# PCB-ACMSLb.net
KiCad netlist of a schematic drawn in EAGLE
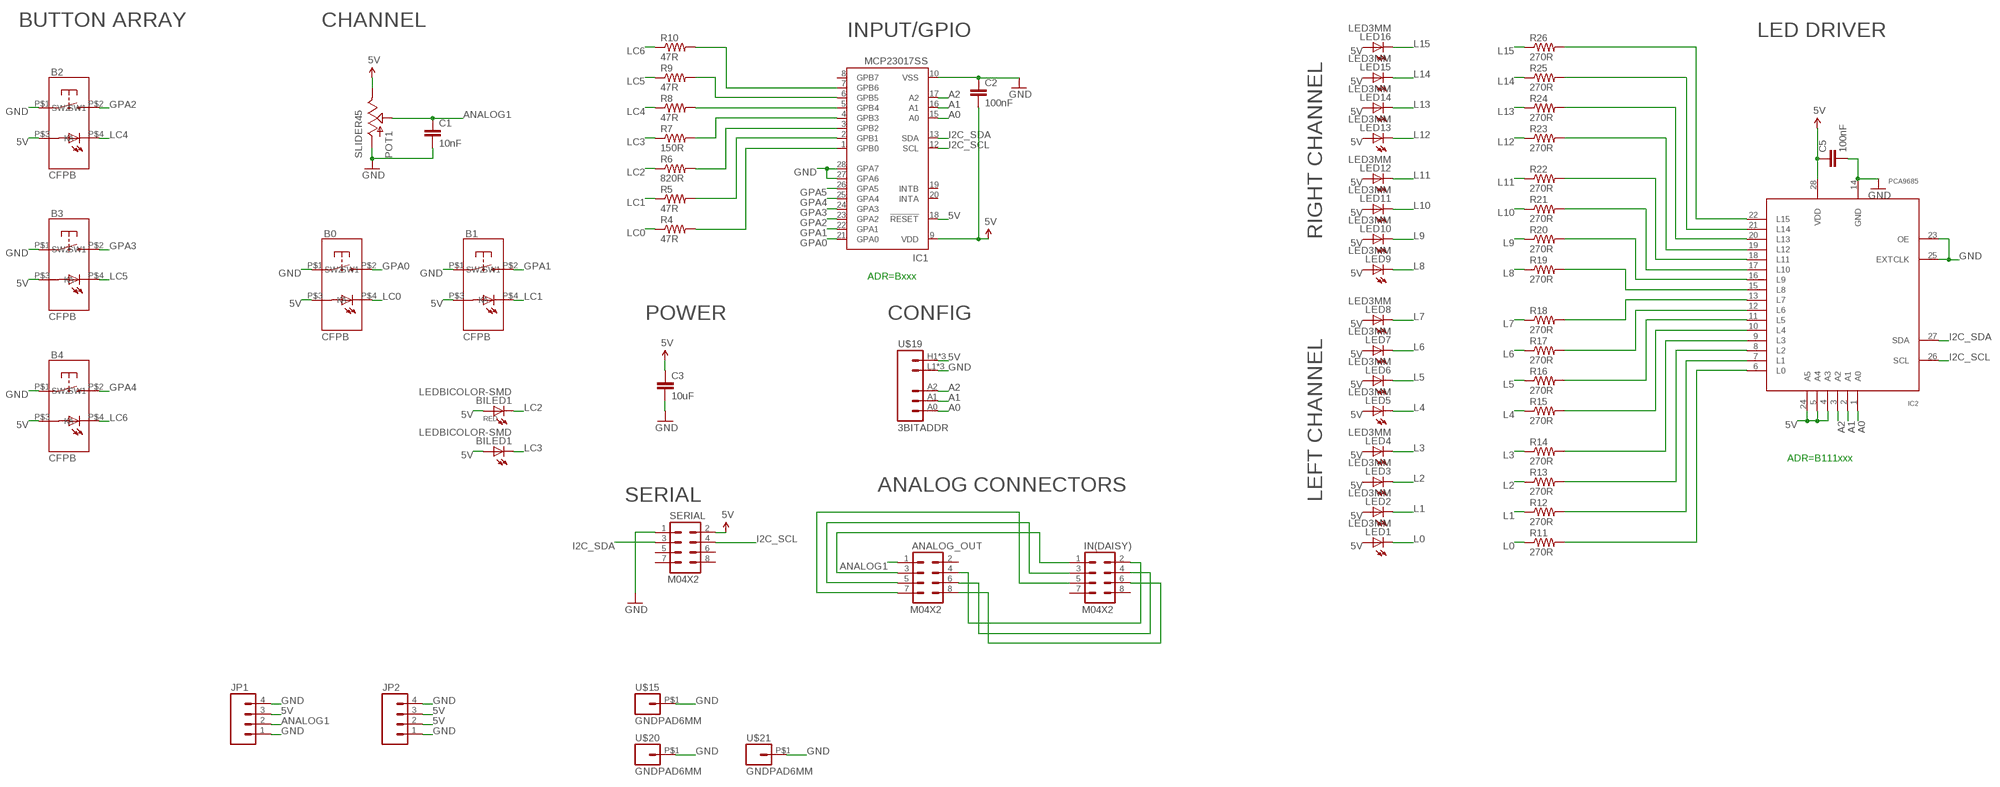
[diagram p0: schematic, sheet 1]

(export (version "E")
  (design (tool "Eeschema 10.0.6"))
  (components
    (comp (ref "ANALOG_OUT")
      (value "M04X2")
      (footprint "eagle-import:2X4")
      (libsource (lib "eagle-import") (part "M04X2"))
    )
    (comp (ref "B0")
      (value "CFPB")
      (footprint "eagle-import:CFPB-6_9MM")
      (libsource (lib "eagle-import") (part "CFPB"))
    )
    (comp (ref "B1")
      (value "CFPB")
      (footprint "eagle-import:CFPB-6_9MM")
      (libsource (lib "eagle-import") (part "CFPB"))
    )
    (comp (ref "B2")
      (value "CFPB")
      (footprint "eagle-import:CFPB-6_9MM")
      (libsource (lib "eagle-import") (part "CFPB"))
    )
    (comp (ref "B3")
      (value "CFPB")
      (footprint "eagle-import:CFPB-6_9MM")
      (libsource (lib "eagle-import") (part "CFPB"))
    )
    (comp (ref "B4")
      (value "CFPB")
      (footprint "eagle-import:CFPB-6_9MM")
      (libsource (lib "eagle-import") (part "CFPB"))
    )
    (comp (ref "BILED1")
      (value "LEDBICOLOR-SMD")
      (footprint "eagle-import:LEDBICOLOR-SMD")
      (libsource (lib "eagle-import") (part "LEDBICOLOR-SMD"))
    )
    (comp (ref "C1")
      (value "10nF")
      (footprint "eagle-import:0603-CAP")
      (libsource (lib "eagle-import") (part "CAP0603-CAP"))
    )
    (comp (ref "C2")
      (value "100nF")
      (footprint "eagle-import:0603-CAP")
      (libsource (lib "eagle-import") (part "CAP0603-CAP"))
    )
    (comp (ref "C3")
      (value "10uF")
      (footprint "eagle-import:0805")
      (libsource (lib "eagle-import") (part "CAP0805"))
    )
    (comp (ref "C5")
      (value "100nF")
      (footprint "eagle-import:0603-CAP")
      (libsource (lib "eagle-import") (part "CAP0603-CAP"))
    )
    (comp (ref "IC1")
      (value "MCP23017SS")
      (footprint "eagle-import:SSOP28")
      (fields
        (field (name "MF") "MICROCHIP")
        (field (name "MPN") "MCP23017-E/SS")
        (field (name "MPN_1") "MCP23017-E/SS")
        (field (name "OC_FARNELL") "1467674")
        (field (name "OC_NEWARK") "31K2960")
      )
      (libsource (lib "eagle-import") (part "MCP23017SS"))
    )
    (comp (ref "IC2")
      (value "PCA9685")
      (footprint "eagle-import:TSSOP28")
      (libsource (lib "eagle-import") (part "PCA9685"))
    )
    (comp (ref "IN(DAISY)")
      (value "M04X2")
      (footprint "eagle-import:2X4")
      (libsource (lib "eagle-import") (part "M04X2"))
    )
    (comp (ref "JP1")
      (value "M04PTH")
      (footprint "eagle-import:1X04")
      (libsource (lib "eagle-import") (part "M04PTH"))
    )
    (comp (ref "JP2")
      (value "M04PTH")
      (footprint "eagle-import:1X04")
      (libsource (lib "eagle-import") (part "M04PTH"))
    )
    (comp (ref "LED1")
      (value "LED3MM")
      (footprint "eagle-import:LED3MM")
      (libsource (lib "eagle-import") (part "LED3MM"))
    )
    (comp (ref "LED2")
      (value "LED3MM")
      (footprint "eagle-import:LED3MM")
      (libsource (lib "eagle-import") (part "LED3MM"))
    )
    (comp (ref "LED3")
      (value "LED3MM")
      (footprint "eagle-import:LED3MM")
      (libsource (lib "eagle-import") (part "LED3MM"))
    )
    (comp (ref "LED4")
      (value "LED3MM")
      (footprint "eagle-import:LED3MM")
      (libsource (lib "eagle-import") (part "LED3MM"))
    )
    (comp (ref "LED5")
      (value "LED3MM")
      (footprint "eagle-import:LED3MM")
      (libsource (lib "eagle-import") (part "LED3MM"))
    )
    (comp (ref "LED6")
      (value "LED3MM")
      (footprint "eagle-import:LED3MM")
      (libsource (lib "eagle-import") (part "LED3MM"))
    )
    (comp (ref "LED7")
      (value "LED3MM")
      (footprint "eagle-import:LED3MM")
      (libsource (lib "eagle-import") (part "LED3MM"))
    )
    (comp (ref "LED8")
      (value "LED3MM")
      (footprint "eagle-import:LED3MM")
      (libsource (lib "eagle-import") (part "LED3MM"))
    )
    (comp (ref "LED9")
      (value "LED3MM")
      (footprint "eagle-import:LED3MM")
      (libsource (lib "eagle-import") (part "LED3MM"))
    )
    (comp (ref "LED10")
      (value "LED3MM")
      (footprint "eagle-import:LED3MM")
      (libsource (lib "eagle-import") (part "LED3MM"))
    )
    (comp (ref "LED11")
      (value "LED3MM")
      (footprint "eagle-import:LED3MM")
      (libsource (lib "eagle-import") (part "LED3MM"))
    )
    (comp (ref "LED12")
      (value "LED3MM")
      (footprint "eagle-import:LED3MM")
      (libsource (lib "eagle-import") (part "LED3MM"))
    )
    (comp (ref "LED13")
      (value "LED3MM")
      (footprint "eagle-import:LED3MM")
      (libsource (lib "eagle-import") (part "LED3MM"))
    )
    (comp (ref "LED14")
      (value "LED3MM")
      (footprint "eagle-import:LED3MM")
      (libsource (lib "eagle-import") (part "LED3MM"))
    )
    (comp (ref "LED15")
      (value "LED3MM")
      (footprint "eagle-import:LED3MM")
      (libsource (lib "eagle-import") (part "LED3MM"))
    )
    (comp (ref "LED16")
      (value "LED3MM")
      (footprint "eagle-import:LED3MM")
      (libsource (lib "eagle-import") (part "LED3MM"))
    )
    (comp (ref "POT1")
      (value "SLIDER45")
      (footprint "eagle-import:SLIDER45")
      (libsource (lib "eagle-import") (part "SLIDER45"))
    )
    (comp (ref "R4")
      (value "47R")
      (footprint "eagle-import:0603-RES")
      (libsource (lib "eagle-import") (part "RESISTOR0603-RES"))
    )
    (comp (ref "R5")
      (value "47R")
      (footprint "eagle-import:0603-RES")
      (libsource (lib "eagle-import") (part "RESISTOR0603-RES"))
    )
    (comp (ref "R6")
      (value "820R")
      (footprint "eagle-import:0603-RES")
      (libsource (lib "eagle-import") (part "RESISTOR0603-RES"))
    )
    (comp (ref "R7")
      (value "150R")
      (footprint "eagle-import:0603-RES")
      (libsource (lib "eagle-import") (part "RESISTOR0603-RES"))
    )
    (comp (ref "R8")
      (value "47R")
      (footprint "eagle-import:0603-RES")
      (libsource (lib "eagle-import") (part "RESISTOR0603-RES"))
    )
    (comp (ref "R9")
      (value "47R")
      (footprint "eagle-import:0603-RES")
      (libsource (lib "eagle-import") (part "RESISTOR0603-RES"))
    )
    (comp (ref "R10")
      (value "47R")
      (footprint "eagle-import:0603-RES")
      (libsource (lib "eagle-import") (part "RESISTOR0603-RES"))
    )
    (comp (ref "R11")
      (value "270R")
      (footprint "eagle-import:0603-RES")
      (libsource (lib "eagle-import") (part "RESISTOR0603-RES"))
    )
    (comp (ref "R12")
      (value "270R")
      (footprint "eagle-import:0603-RES")
      (libsource (lib "eagle-import") (part "RESISTOR0603-RES"))
    )
    (comp (ref "R13")
      (value "270R")
      (footprint "eagle-import:0603-RES")
      (libsource (lib "eagle-import") (part "RESISTOR0603-RES"))
    )
    (comp (ref "R14")
      (value "270R")
      (footprint "eagle-import:0603-RES")
      (libsource (lib "eagle-import") (part "RESISTOR0603-RES"))
    )
    (comp (ref "R15")
      (value "270R")
      (footprint "eagle-import:0603-RES")
      (libsource (lib "eagle-import") (part "RESISTOR0603-RES"))
    )
    (comp (ref "R16")
      (value "270R")
      (footprint "eagle-import:0603-RES")
      (libsource (lib "eagle-import") (part "RESISTOR0603-RES"))
    )
    (comp (ref "R17")
      (value "270R")
      (footprint "eagle-import:0603-RES")
      (libsource (lib "eagle-import") (part "RESISTOR0603-RES"))
    )
    (comp (ref "R18")
      (value "270R")
      (footprint "eagle-import:0603-RES")
      (libsource (lib "eagle-import") (part "RESISTOR0603-RES"))
    )
    (comp (ref "R19")
      (value "270R")
      (footprint "eagle-import:0603-RES")
      (libsource (lib "eagle-import") (part "RESISTOR0603-RES"))
    )
    (comp (ref "R20")
      (value "270R")
      (footprint "eagle-import:0603-RES")
      (libsource (lib "eagle-import") (part "RESISTOR0603-RES"))
    )
    (comp (ref "R21")
      (value "270R")
      (footprint "eagle-import:0603-RES")
      (libsource (lib "eagle-import") (part "RESISTOR0603-RES"))
    )
    (comp (ref "R22")
      (value "270R")
      (footprint "eagle-import:0603-RES")
      (libsource (lib "eagle-import") (part "RESISTOR0603-RES"))
    )
    (comp (ref "R23")
      (value "270R")
      (footprint "eagle-import:0603-RES")
      (libsource (lib "eagle-import") (part "RESISTOR0603-RES"))
    )
    (comp (ref "R24")
      (value "270R")
      (footprint "eagle-import:0603-RES")
      (libsource (lib "eagle-import") (part "RESISTOR0603-RES"))
    )
    (comp (ref "R25")
      (value "270R")
      (footprint "eagle-import:0603-RES")
      (libsource (lib "eagle-import") (part "RESISTOR0603-RES"))
    )
    (comp (ref "R26")
      (value "270R")
      (footprint "eagle-import:0603-RES")
      (libsource (lib "eagle-import") (part "RESISTOR0603-RES"))
    )
    (comp (ref "SERIAL")
      (value "M04X2")
      (footprint "eagle-import:2X4")
      (libsource (lib "eagle-import") (part "M04X2"))
    )
    (comp (ref "U$15")
      (value "GNDPAD6MM")
      (footprint "eagle-import:3.2MMPAD6MM")
      (libsource (lib "eagle-import") (part "GNDPAD6MM"))
    )
    (comp (ref "U$19")
      (value "3BITADDR")
      (footprint "eagle-import:3BITADDR")
      (libsource (lib "eagle-import") (part "3BITADDR"))
    )
    (comp (ref "U$20")
      (value "GNDPAD6MM")
      (footprint "eagle-import:3.2MMPAD6MM")
      (libsource (lib "eagle-import") (part "GNDPAD6MM"))
    )
    (comp (ref "U$21")
      (value "GNDPAD6MM")
      (footprint "eagle-import:3.2MMPAD6MM")
      (libsource (lib "eagle-import") (part "GNDPAD6MM"))
    )
  )
  (nets
    (net (code "1") (name "/A0") (class "Default")
      (node (ref "IC1") (pin "15") (pinfunction "A0_15") (pintype "input"))
      (node (ref "IC2") (pin "1") (pinfunction "A0_1") (pintype "input"))
      (node (ref "U$19") (pin "A0") (pinfunction "A0_A0") (pintype "passive"))
    )
    (net (code "2") (name "/A1") (class "Default")
      (node (ref "IC1") (pin "16") (pinfunction "A1_16") (pintype "input"))
      (node (ref "IC2") (pin "2") (pinfunction "A1_2") (pintype "input"))
      (node (ref "U$19") (pin "A1") (pinfunction "A1_A1") (pintype "passive"))
    )
    (net (code "3") (name "/A2") (class "Default")
      (node (ref "IC1") (pin "17") (pinfunction "A2_17") (pintype "input"))
      (node (ref "IC2") (pin "3") (pinfunction "A2_3") (pintype "input"))
      (node (ref "U$19") (pin "A2") (pinfunction "A2_A2") (pintype "passive"))
    )
    (net (code "4") (name "/ANALOG1") (class "Default")
      (node (ref "ANALOG_OUT") (pin "1") (pinfunction "1_1") (pintype "passive"))
      (node (ref "C1") (pin "1") (pinfunction "1_1") (pintype "passive"))
      (node (ref "JP1") (pin "2") (pinfunction "2_2") (pintype "passive"))
      (node (ref "POT1") (pin "2A") (pinfunction "S_2A") (pintype "passive"))
    )
    (net (code "5") (name "/GPA0") (class "Default")
      (node (ref "B0") (pin "P$2") (pinfunction "SW2_P$2") (pintype "bidirectional"))
      (node (ref "IC1") (pin "21") (pinfunction "GPA0_21") (pintype "bidirectional"))
    )
    (net (code "6") (name "/GPA1") (class "Default")
      (node (ref "B1") (pin "P$2") (pinfunction "SW2_P$2") (pintype "bidirectional"))
      (node (ref "IC1") (pin "22") (pinfunction "GPA1_22") (pintype "bidirectional"))
    )
    (net (code "7") (name "/GPA2") (class "Default")
      (node (ref "B2") (pin "P$2") (pinfunction "SW2_P$2") (pintype "bidirectional"))
      (node (ref "IC1") (pin "23") (pinfunction "GPA2_23") (pintype "bidirectional"))
    )
    (net (code "8") (name "/GPA3") (class "Default")
      (node (ref "B3") (pin "P$2") (pinfunction "SW2_P$2") (pintype "bidirectional"))
      (node (ref "IC1") (pin "24") (pinfunction "GPA3_24") (pintype "bidirectional"))
    )
    (net (code "9") (name "/GPA4") (class "Default")
      (node (ref "B4") (pin "P$2") (pinfunction "SW2_P$2") (pintype "bidirectional"))
      (node (ref "IC1") (pin "25") (pinfunction "GPA4_25") (pintype "bidirectional"))
    )
    (net (code "10") (name "/GPA5") (class "Default")
      (node (ref "IC1") (pin "26") (pinfunction "GPA5_26") (pintype "bidirectional"))
    )
    (net (code "11") (name "/I2C_SCL") (class "Default")
      (node (ref "IC1") (pin "12") (pinfunction "SCL_12") (pintype "input"))
      (node (ref "IC2") (pin "26") (pinfunction "SCL_26") (pintype "input"))
      (node (ref "SERIAL") (pin "4") (pinfunction "4_4") (pintype "passive"))
    )
    (net (code "12") (name "/I2C_SDA") (class "Default")
      (node (ref "IC1") (pin "13") (pinfunction "SDA_13") (pintype "bidirectional"))
      (node (ref "IC2") (pin "27") (pinfunction "SDA_27") (pintype "input"))
      (node (ref "SERIAL") (pin "3") (pinfunction "3_3") (pintype "passive"))
    )
    (net (code "13") (name "/L0") (class "Default")
      (node (ref "LED1") (pin "K") (pinfunction "C_K") (pintype "passive"))
      (node (ref "R11") (pin "1") (pinfunction "1_1") (pintype "passive"))
    )
    (net (code "14") (name "/L1") (class "Default")
      (node (ref "LED2") (pin "K") (pinfunction "C_K") (pintype "passive"))
      (node (ref "R12") (pin "1") (pinfunction "1_1") (pintype "passive"))
    )
    (net (code "15") (name "/L2") (class "Default")
      (node (ref "LED3") (pin "K") (pinfunction "C_K") (pintype "passive"))
      (node (ref "R13") (pin "1") (pinfunction "1_1") (pintype "passive"))
    )
    (net (code "16") (name "/L3") (class "Default")
      (node (ref "LED4") (pin "K") (pinfunction "C_K") (pintype "passive"))
      (node (ref "R14") (pin "1") (pinfunction "1_1") (pintype "passive"))
    )
    (net (code "17") (name "/L4") (class "Default")
      (node (ref "LED5") (pin "K") (pinfunction "C_K") (pintype "passive"))
      (node (ref "R15") (pin "1") (pinfunction "1_1") (pintype "passive"))
    )
    (net (code "18") (name "/L5") (class "Default")
      (node (ref "LED6") (pin "K") (pinfunction "C_K") (pintype "passive"))
      (node (ref "R16") (pin "1") (pinfunction "1_1") (pintype "passive"))
    )
    (net (code "19") (name "/L6") (class "Default")
      (node (ref "LED7") (pin "K") (pinfunction "C_K") (pintype "passive"))
      (node (ref "R17") (pin "1") (pinfunction "1_1") (pintype "passive"))
    )
    (net (code "20") (name "/L7") (class "Default")
      (node (ref "LED8") (pin "K") (pinfunction "C_K") (pintype "passive"))
      (node (ref "R18") (pin "1") (pinfunction "1_1") (pintype "passive"))
    )
    (net (code "21") (name "/L8") (class "Default")
      (node (ref "LED9") (pin "K") (pinfunction "C_K") (pintype "passive"))
      (node (ref "R19") (pin "1") (pinfunction "1_1") (pintype "passive"))
    )
    (net (code "22") (name "/L9") (class "Default")
      (node (ref "LED10") (pin "K") (pinfunction "C_K") (pintype "passive"))
      (node (ref "R20") (pin "1") (pinfunction "1_1") (pintype "passive"))
    )
    (net (code "23") (name "/L10") (class "Default")
      (node (ref "LED11") (pin "K") (pinfunction "C_K") (pintype "passive"))
      (node (ref "R21") (pin "1") (pinfunction "1_1") (pintype "passive"))
    )
    (net (code "24") (name "/L11") (class "Default")
      (node (ref "LED12") (pin "K") (pinfunction "C_K") (pintype "passive"))
      (node (ref "R22") (pin "1") (pinfunction "1_1") (pintype "passive"))
    )
    (net (code "25") (name "/L12") (class "Default")
      (node (ref "LED13") (pin "K") (pinfunction "C_K") (pintype "passive"))
      (node (ref "R23") (pin "1") (pinfunction "1_1") (pintype "passive"))
    )
    (net (code "26") (name "/L13") (class "Default")
      (node (ref "LED14") (pin "K") (pinfunction "C_K") (pintype "passive"))
      (node (ref "R24") (pin "1") (pinfunction "1_1") (pintype "passive"))
    )
    (net (code "27") (name "/L14") (class "Default")
      (node (ref "LED15") (pin "K") (pinfunction "C_K") (pintype "passive"))
      (node (ref "R25") (pin "1") (pinfunction "1_1") (pintype "passive"))
    )
    (net (code "28") (name "/L15") (class "Default")
      (node (ref "LED16") (pin "K") (pinfunction "C_K") (pintype "passive"))
      (node (ref "R26") (pin "1") (pinfunction "1_1") (pintype "passive"))
    )
    (net (code "29") (name "/LC0") (class "Default")
      (node (ref "B0") (pin "P$4") (pinfunction "K_P$4") (pintype "bidirectional"))
      (node (ref "R4") (pin "1") (pinfunction "1_1") (pintype "passive"))
    )
    (net (code "30") (name "/LC1") (class "Default")
      (node (ref "B1") (pin "P$4") (pinfunction "K_P$4") (pintype "bidirectional"))
      (node (ref "R5") (pin "1") (pinfunction "1_1") (pintype "passive"))
    )
    (net (code "31") (name "/LC2") (class "Default")
      (node (ref "BILED1") (pin "P$2") (pinfunction "C_P$2") (pintype "passive"))
      (node (ref "R6") (pin "1") (pinfunction "1_1") (pintype "passive"))
    )
    (net (code "32") (name "/LC3") (class "Default")
      (node (ref "BILED1") (pin "P$4") (pinfunction "C1_P$4") (pintype "passive"))
      (node (ref "R7") (pin "1") (pinfunction "1_1") (pintype "passive"))
    )
    (net (code "33") (name "/LC4") (class "Default")
      (node (ref "B2") (pin "P$4") (pinfunction "K_P$4") (pintype "bidirectional"))
      (node (ref "R8") (pin "1") (pinfunction "1_1") (pintype "passive"))
    )
    (net (code "34") (name "/LC5") (class "Default")
      (node (ref "B3") (pin "P$4") (pinfunction "K_P$4") (pintype "bidirectional"))
      (node (ref "R9") (pin "1") (pinfunction "1_1") (pintype "passive"))
    )
    (net (code "35") (name "/LC6") (class "Default")
      (node (ref "B4") (pin "P$4") (pinfunction "K_P$4") (pintype "bidirectional"))
      (node (ref "R10") (pin "1") (pinfunction "1_1") (pintype "passive"))
    )
    (net (code "36") (name "5V") (class "Default")
      (node (ref "B0") (pin "P$3") (pinfunction "A_P$3") (pintype "bidirectional"))
      (node (ref "B1") (pin "P$3") (pinfunction "A_P$3") (pintype "bidirectional"))
      (node (ref "B2") (pin "P$3") (pinfunction "A_P$3") (pintype "bidirectional"))
      (node (ref "B3") (pin "P$3") (pinfunction "A_P$3") (pintype "bidirectional"))
      (node (ref "B4") (pin "P$3") (pinfunction "A_P$3") (pintype "bidirectional"))
      (node (ref "BILED1") (pin "P$1") (pinfunction "A_P$1") (pintype "passive"))
      (node (ref "BILED1") (pin "P$3") (pinfunction "A1_P$3") (pintype "passive"))
      (node (ref "C2") (pin "2") (pinfunction "2_2") (pintype "passive"))
      (node (ref "C3") (pin "1") (pinfunction "1_1") (pintype "passive"))
      (node (ref "C5") (pin "1") (pinfunction "1_1") (pintype "passive"))
      (node (ref "IC1") (pin "18") (pinfunction "~{RESET}_18") (pintype "input"))
      (node (ref "IC1") (pin "9") (pinfunction "VDD_9") (pintype "power_in"))
      (node (ref "IC2") (pin "24") (pinfunction "A5_24") (pintype "input"))
      (node (ref "IC2") (pin "28") (pinfunction "VDD_28") (pintype "power_in"))
      (node (ref "IC2") (pin "4") (pinfunction "A3_4") (pintype "input"))
      (node (ref "IC2") (pin "5") (pinfunction "A4_5") (pintype "input"))
      (node (ref "JP1") (pin "3") (pinfunction "3_3") (pintype "passive"))
      (node (ref "JP2") (pin "2") (pinfunction "2_2") (pintype "passive"))
      (node (ref "JP2") (pin "3") (pinfunction "3_3") (pintype "passive"))
      (node (ref "LED1") (pin "A") (pinfunction "A_A") (pintype "passive"))
      (node (ref "LED10") (pin "A") (pinfunction "A_A") (pintype "passive"))
      (node (ref "LED11") (pin "A") (pinfunction "A_A") (pintype "passive"))
      (node (ref "LED12") (pin "A") (pinfunction "A_A") (pintype "passive"))
      (node (ref "LED13") (pin "A") (pinfunction "A_A") (pintype "passive"))
      (node (ref "LED14") (pin "A") (pinfunction "A_A") (pintype "passive"))
      (node (ref "LED15") (pin "A") (pinfunction "A_A") (pintype "passive"))
      (node (ref "LED16") (pin "A") (pinfunction "A_A") (pintype "passive"))
      (node (ref "LED2") (pin "A") (pinfunction "A_A") (pintype "passive"))
      (node (ref "LED3") (pin "A") (pinfunction "A_A") (pintype "passive"))
      (node (ref "LED4") (pin "A") (pinfunction "A_A") (pintype "passive"))
      (node (ref "LED5") (pin "A") (pinfunction "A_A") (pintype "passive"))
      (node (ref "LED6") (pin "A") (pinfunction "A_A") (pintype "passive"))
      (node (ref "LED7") (pin "A") (pinfunction "A_A") (pintype "passive"))
      (node (ref "LED8") (pin "A") (pinfunction "A_A") (pintype "passive"))
      (node (ref "LED9") (pin "A") (pinfunction "A_A") (pintype "passive"))
      (node (ref "POT1") (pin "1") (pinfunction "E_1") (pintype "passive"))
      (node (ref "SERIAL") (pin "2") (pinfunction "2_2") (pintype "passive"))
      (node (ref "U$19") (pin "H1") (pinfunction "VCC_H1") (pintype "passive"))
      (node (ref "U$19") (pin "H2") (pinfunction "VCC_H2") (pintype "passive"))
      (node (ref "U$19") (pin "H3") (pinfunction "VCC_H3") (pintype "passive"))
    )
    (net (code "37") (name "GND") (class "Default")
      (node (ref "B0") (pin "P$1") (pinfunction "SW1_P$1") (pintype "bidirectional"))
      (node (ref "B1") (pin "P$1") (pinfunction "SW1_P$1") (pintype "bidirectional"))
      (node (ref "B2") (pin "P$1") (pinfunction "SW1_P$1") (pintype "bidirectional"))
      (node (ref "B3") (pin "P$1") (pinfunction "SW1_P$1") (pintype "bidirectional"))
      (node (ref "B4") (pin "P$1") (pinfunction "SW1_P$1") (pintype "bidirectional"))
      (node (ref "C1") (pin "2") (pinfunction "2_2") (pintype "passive"))
      (node (ref "C2") (pin "1") (pinfunction "1_1") (pintype "passive"))
      (node (ref "C3") (pin "2") (pinfunction "2_2") (pintype "passive"))
      (node (ref "C5") (pin "2") (pinfunction "2_2") (pintype "passive"))
      (node (ref "IC1") (pin "10") (pinfunction "VSS_10") (pintype "power_in"))
      (node (ref "IC1") (pin "27") (pinfunction "GPA6_27") (pintype "bidirectional"))
      (node (ref "IC1") (pin "28") (pinfunction "GPA7_28") (pintype "bidirectional"))
      (node (ref "IC2") (pin "14") (pinfunction "GND_14") (pintype "power_in"))
      (node (ref "IC2") (pin "23") (pinfunction "OE_23") (pintype "input"))
      (node (ref "IC2") (pin "25") (pinfunction "EXTCLK_25") (pintype "input"))
      (node (ref "JP1") (pin "1") (pinfunction "1_1") (pintype "passive"))
      (node (ref "JP1") (pin "4") (pinfunction "4_4") (pintype "passive"))
      (node (ref "JP2") (pin "1") (pinfunction "1_1") (pintype "passive"))
      (node (ref "JP2") (pin "4") (pinfunction "4_4") (pintype "passive"))
      (node (ref "POT1") (pin "3") (pinfunction "A_3") (pintype "passive"))
      (node (ref "SERIAL") (pin "1") (pinfunction "1_1") (pintype "passive"))
      (node (ref "U$15") (pin "P$1") (pinfunction "1_P$1") (pintype "passive"))
      (node (ref "U$19") (pin "L1") (pinfunction "GND_L1") (pintype "passive"))
      (node (ref "U$19") (pin "L2") (pinfunction "GND_L2") (pintype "passive"))
      (node (ref "U$19") (pin "L3") (pinfunction "GND_L3") (pintype "passive"))
      (node (ref "U$20") (pin "P$1") (pinfunction "1_P$1") (pintype "passive"))
      (node (ref "U$21") (pin "P$1") (pinfunction "1_P$1") (pintype "passive"))
    )
    (net (code "38") (name "Net-(ANALOG_OUT-Pad3)") (class "Default")
      (node (ref "ANALOG_OUT") (pin "3") (pinfunction "3_3") (pintype "passive"))
      (node (ref "IN(DAISY)") (pin "1") (pinfunction "1_1") (pintype "passive"))
    )
    (net (code "39") (name "Net-(ANALOG_OUT-Pad4)") (class "Default")
      (node (ref "ANALOG_OUT") (pin "4") (pinfunction "4_4") (pintype "passive"))
      (node (ref "IN(DAISY)") (pin "2") (pinfunction "2_2") (pintype "passive"))
    )
    (net (code "40") (name "Net-(ANALOG_OUT-Pad5)") (class "Default")
      (node (ref "ANALOG_OUT") (pin "5") (pinfunction "5_5") (pintype "passive"))
      (node (ref "IN(DAISY)") (pin "3") (pinfunction "3_3") (pintype "passive"))
    )
    (net (code "41") (name "Net-(ANALOG_OUT-Pad6)") (class "Default")
      (node (ref "ANALOG_OUT") (pin "6") (pinfunction "6_6") (pintype "passive"))
      (node (ref "IN(DAISY)") (pin "4") (pinfunction "4_4") (pintype "passive"))
    )
    (net (code "42") (name "Net-(ANALOG_OUT-Pad7)") (class "Default")
      (node (ref "ANALOG_OUT") (pin "7") (pinfunction "7_7") (pintype "passive"))
      (node (ref "IN(DAISY)") (pin "5") (pinfunction "5_5") (pintype "passive"))
    )
    (net (code "43") (name "Net-(ANALOG_OUT-Pad8)") (class "Default")
      (node (ref "ANALOG_OUT") (pin "8") (pinfunction "8_8") (pintype "passive"))
      (node (ref "IN(DAISY)") (pin "6") (pinfunction "6_6") (pintype "passive"))
    )
    (net (code "44") (name "Net-(IC1-GPB0)") (class "Default")
      (node (ref "IC1") (pin "1") (pinfunction "GPB0_1") (pintype "bidirectional"))
      (node (ref "R4") (pin "2") (pinfunction "2_2") (pintype "passive"))
    )
    (net (code "45") (name "Net-(IC1-GPB1)") (class "Default")
      (node (ref "IC1") (pin "2") (pinfunction "GPB1_2") (pintype "bidirectional"))
      (node (ref "R5") (pin "2") (pinfunction "2_2") (pintype "passive"))
    )
    (net (code "46") (name "Net-(IC1-GPB2)") (class "Default")
      (node (ref "IC1") (pin "3") (pinfunction "GPB2_3") (pintype "bidirectional"))
      (node (ref "R6") (pin "2") (pinfunction "2_2") (pintype "passive"))
    )
    (net (code "47") (name "Net-(IC1-GPB3)") (class "Default")
      (node (ref "IC1") (pin "4") (pinfunction "GPB3_4") (pintype "bidirectional"))
      (node (ref "R7") (pin "2") (pinfunction "2_2") (pintype "passive"))
    )
    (net (code "48") (name "Net-(IC1-GPB4)") (class "Default")
      (node (ref "IC1") (pin "5") (pinfunction "GPB4_5") (pintype "bidirectional"))
      (node (ref "R8") (pin "2") (pinfunction "2_2") (pintype "passive"))
    )
    (net (code "49") (name "Net-(IC1-GPB5)") (class "Default")
      (node (ref "IC1") (pin "6") (pinfunction "GPB5_6") (pintype "bidirectional"))
      (node (ref "R9") (pin "2") (pinfunction "2_2") (pintype "passive"))
    )
    (net (code "50") (name "Net-(IC1-GPB6)") (class "Default")
      (node (ref "IC1") (pin "7") (pinfunction "GPB6_7") (pintype "bidirectional"))
      (node (ref "R10") (pin "2") (pinfunction "2_2") (pintype "passive"))
    )
    (net (code "51") (name "Net-(IC2-L0)") (class "Default")
      (node (ref "IC2") (pin "6") (pinfunction "L0_6") (pintype "output"))
      (node (ref "R11") (pin "2") (pinfunction "2_2") (pintype "passive"))
    )
    (net (code "52") (name "Net-(IC2-L1)") (class "Default")
      (node (ref "IC2") (pin "7") (pinfunction "L1_7") (pintype "output"))
      (node (ref "R12") (pin "2") (pinfunction "2_2") (pintype "passive"))
    )
    (net (code "53") (name "Net-(IC2-L2)") (class "Default")
      (node (ref "IC2") (pin "8") (pinfunction "L2_8") (pintype "output"))
      (node (ref "R13") (pin "2") (pinfunction "2_2") (pintype "passive"))
    )
    (net (code "54") (name "Net-(IC2-L3)") (class "Default")
      (node (ref "IC2") (pin "9") (pinfunction "L3_9") (pintype "output"))
      (node (ref "R14") (pin "2") (pinfunction "2_2") (pintype "passive"))
    )
    (net (code "55") (name "Net-(IC2-L4)") (class "Default")
      (node (ref "IC2") (pin "10") (pinfunction "L4_10") (pintype "output"))
      (node (ref "R15") (pin "2") (pinfunction "2_2") (pintype "passive"))
    )
    (net (code "56") (name "Net-(IC2-L5)") (class "Default")
      (node (ref "IC2") (pin "11") (pinfunction "L5_11") (pintype "output"))
      (node (ref "R16") (pin "2") (pinfunction "2_2") (pintype "passive"))
    )
    (net (code "57") (name "Net-(IC2-L6)") (class "Default")
      (node (ref "IC2") (pin "12") (pinfunction "L6_12") (pintype "output"))
      (node (ref "R17") (pin "2") (pinfunction "2_2") (pintype "passive"))
    )
    (net (code "58") (name "Net-(IC2-L7)") (class "Default")
      (node (ref "IC2") (pin "13") (pinfunction "L7_13") (pintype "output"))
      (node (ref "R18") (pin "2") (pinfunction "2_2") (pintype "passive"))
    )
    (net (code "59") (name "Net-(IC2-L8)") (class "Default")
      (node (ref "IC2") (pin "15") (pinfunction "L8_15") (pintype "output"))
      (node (ref "R19") (pin "2") (pinfunction "2_2") (pintype "passive"))
    )
    (net (code "60") (name "Net-(IC2-L9)") (class "Default")
      (node (ref "IC2") (pin "16") (pinfunction "L9_16") (pintype "output"))
      (node (ref "R20") (pin "2") (pinfunction "2_2") (pintype "passive"))
    )
    (net (code "61") (name "Net-(IC2-L10)") (class "Default")
      (node (ref "IC2") (pin "17") (pinfunction "L10_17") (pintype "output"))
      (node (ref "R21") (pin "2") (pinfunction "2_2") (pintype "passive"))
    )
    (net (code "62") (name "Net-(IC2-L11)") (class "Default")
      (node (ref "IC2") (pin "18") (pinfunction "L11_18") (pintype "output"))
      (node (ref "R22") (pin "2") (pinfunction "2_2") (pintype "passive"))
    )
    (net (code "63") (name "Net-(IC2-L12)") (class "Default")
      (node (ref "IC2") (pin "19") (pinfunction "L12_19") (pintype "output"))
      (node (ref "R23") (pin "2") (pinfunction "2_2") (pintype "passive"))
    )
    (net (code "64") (name "Net-(IC2-L13)") (class "Default")
      (node (ref "IC2") (pin "20") (pinfunction "L13_20") (pintype "output"))
      (node (ref "R24") (pin "2") (pinfunction "2_2") (pintype "passive"))
    )
    (net (code "65") (name "Net-(IC2-L14)") (class "Default")
      (node (ref "IC2") (pin "21") (pinfunction "L14_21") (pintype "output"))
      (node (ref "R25") (pin "2") (pinfunction "2_2") (pintype "passive"))
    )
    (net (code "66") (name "Net-(IC2-L15)") (class "Default")
      (node (ref "IC2") (pin "22") (pinfunction "L15_22") (pintype "output"))
      (node (ref "R26") (pin "2") (pinfunction "2_2") (pintype "passive"))
    )
    (net (code "67") (name "unconnected-(ANALOG_OUT-Pad2)") (class "Default")
      (node (ref "ANALOG_OUT") (pin "2") (pinfunction "2_2") (pintype "passive"))
    )
    (net (code "68") (name "unconnected-(IC1-GPB7-Pad8)") (class "Default")
      (node (ref "IC1") (pin "8") (pinfunction "GPB7_8") (pintype "bidirectional"))
    )
    (net (code "69") (name "unconnected-(IC1-INTA-Pad20)") (class "Default")
      (node (ref "IC1") (pin "20") (pinfunction "INTA_20") (pintype "output"))
    )
    (net (code "70") (name "unconnected-(IC1-INTB-Pad19)") (class "Default")
      (node (ref "IC1") (pin "19") (pinfunction "INTB_19") (pintype "output"))
    )
    (net (code "71") (name "unconnected-(IN(DAISY)-Pad7)") (class "Default")
      (node (ref "IN(DAISY)") (pin "7") (pinfunction "7_7") (pintype "passive"))
    )
    (net (code "72") (name "unconnected-(IN(DAISY)-Pad8)") (class "Default")
      (node (ref "IN(DAISY)") (pin "8") (pinfunction "8_8") (pintype "passive"))
    )
    (net (code "73") (name "unconnected-(SERIAL-Pad5)") (class "Default")
      (node (ref "SERIAL") (pin "5") (pinfunction "5_5") (pintype "passive"))
    )
    (net (code "74") (name "unconnected-(SERIAL-Pad6)") (class "Default")
      (node (ref "SERIAL") (pin "6") (pinfunction "6_6") (pintype "passive"))
    )
    (net (code "75") (name "unconnected-(SERIAL-Pad7)") (class "Default")
      (node (ref "SERIAL") (pin "7") (pinfunction "7_7") (pintype "passive"))
    )
    (net (code "76") (name "unconnected-(SERIAL-Pad8)") (class "Default")
      (node (ref "SERIAL") (pin "8") (pinfunction "8_8") (pintype "passive"))
    )
  )
)
